# IrDA_Contador_v1_0.net
KiCad netlist of a schematic drawn in EAGLE
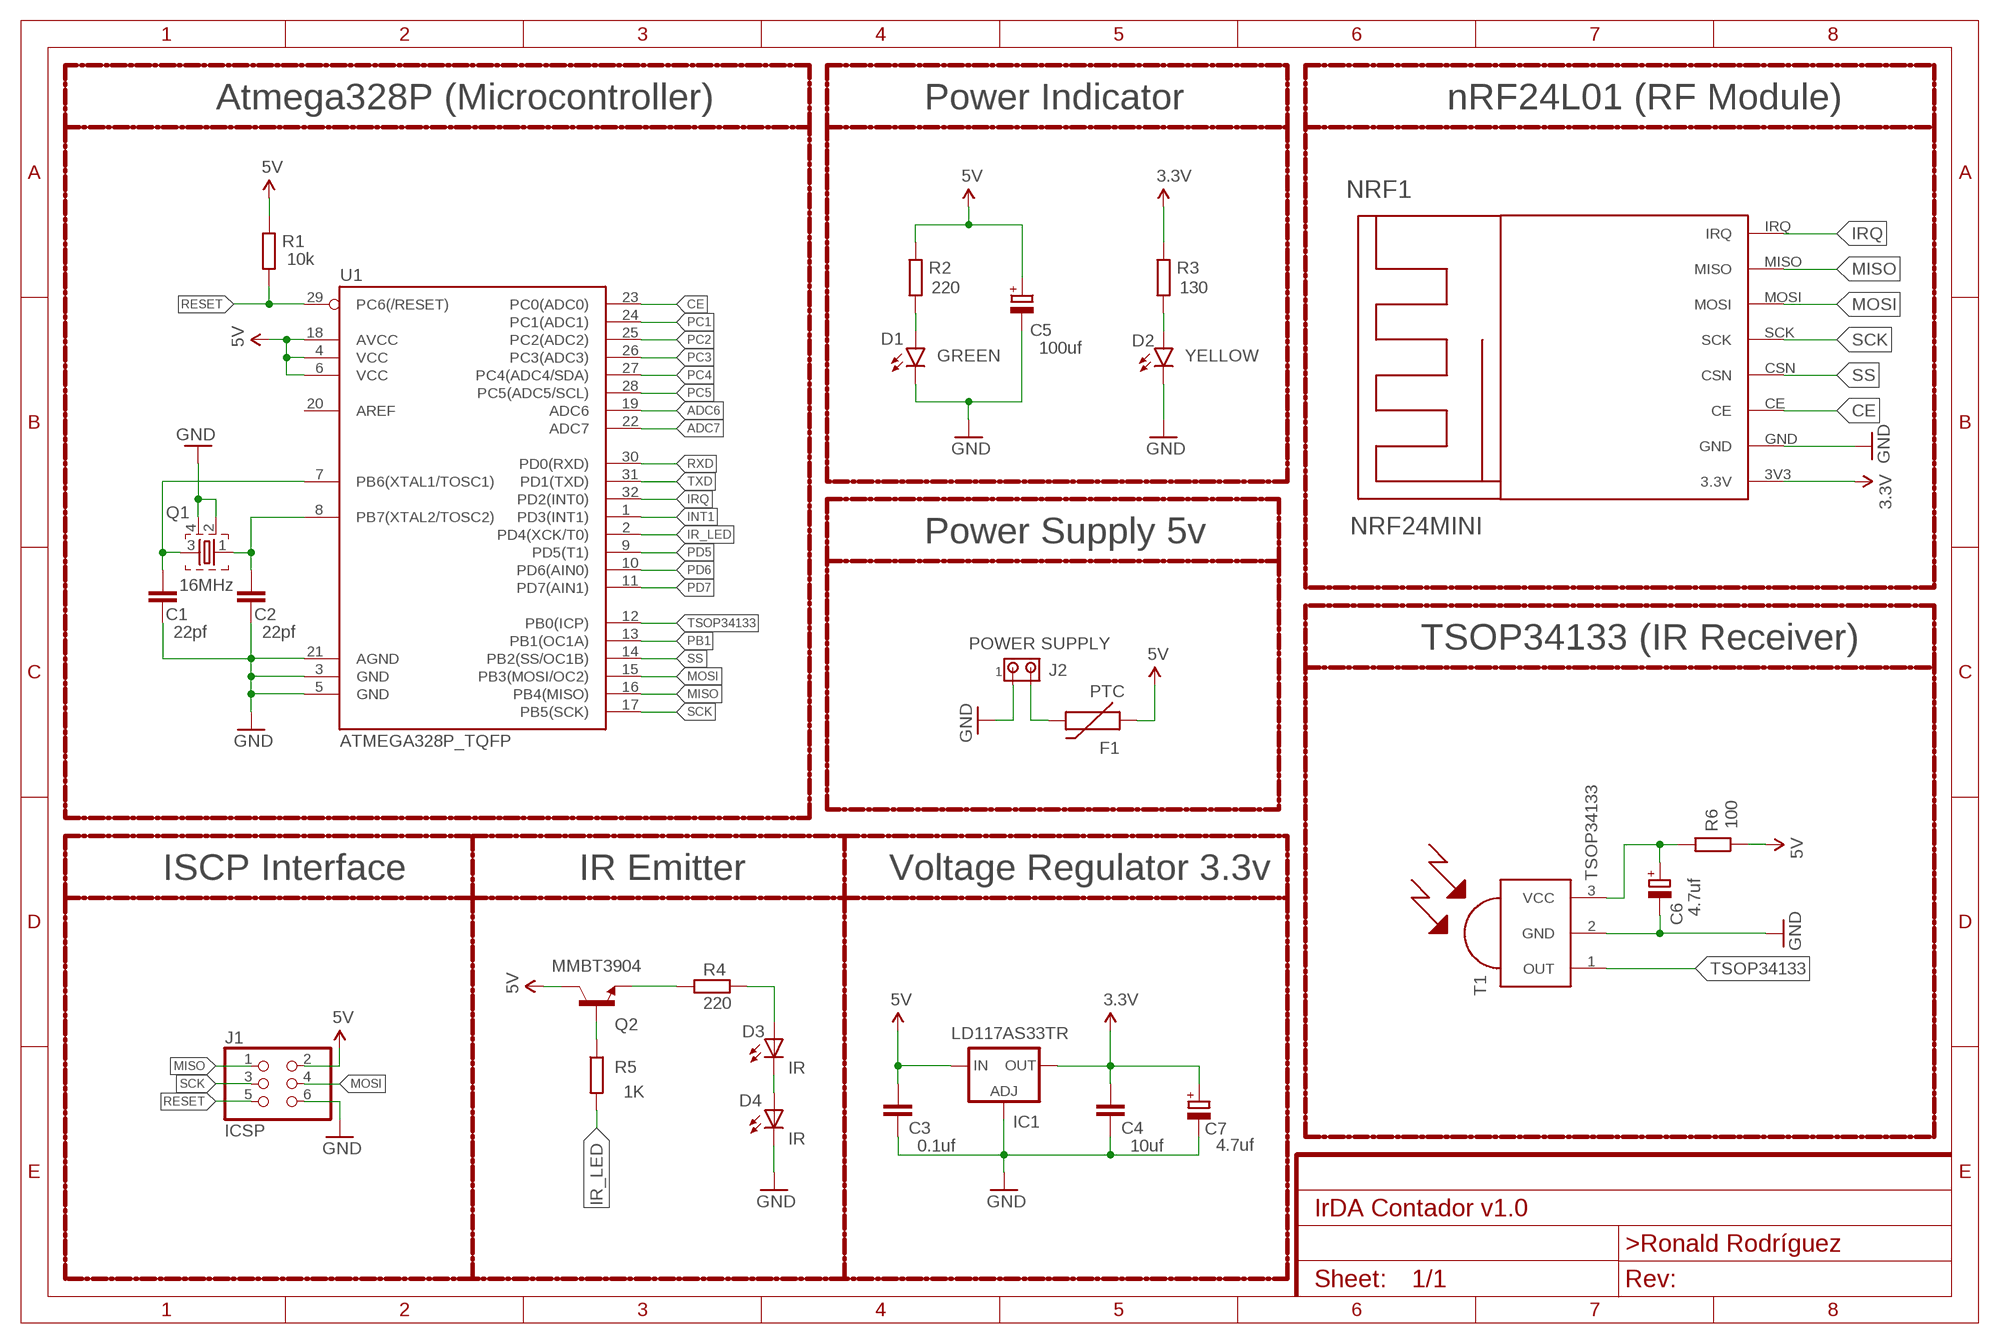
[diagram p0: schematic, sheet 1]

(export (version "E")
  (design (tool "Eeschema 10.0.6"))
  (components
    (comp (ref "C1")
      (value "22pf")
      (footprint "eagle-import:C0603")
      (libsource (lib "eagle-import") (part "C-EUC0603"))
    )
    (comp (ref "C2")
      (value "22pf")
      (footprint "eagle-import:C0603")
      (libsource (lib "eagle-import") (part "C-EUC0603"))
    )
    (comp (ref "C3")
      (value "0.1uf")
      (footprint "eagle-import:C0603")
      (libsource (lib "eagle-import") (part "C-EUC0603"))
    )
    (comp (ref "C4")
      (value "10uf")
      (footprint "eagle-import:C0603")
      (libsource (lib "eagle-import") (part "C-EUC0603"))
    )
    (comp (ref "C5")
      (value "100uf")
      (footprint "eagle-import:153CLV-0605")
      (libsource (lib "eagle-import") (part "CPOL-EU153CLV-0605"))
    )
    (comp (ref "C6")
      (value "4.7uf")
      (footprint "eagle-import:SMC_A")
      (libsource (lib "eagle-import") (part "resistor_CPOL-EUSMCA"))
    )
    (comp (ref "C7")
      (value "4.7uf")
      (footprint "eagle-import:SMC_A")
      (libsource (lib "eagle-import") (part "resistor_CPOL-EUSMCA"))
    )
    (comp (ref "D1")
      (value "GREEN")
      (footprint "eagle-import:LED-0603")
      (libsource (lib "eagle-import") (part "LED-BLUE0603"))
    )
    (comp (ref "D2")
      (value "YELLOW")
      (footprint "eagle-import:LED-0603")
      (libsource (lib "eagle-import") (part "LED-GREEN0603"))
    )
    (comp (ref "D3")
      (value "IR")
      (footprint "eagle-import:LED5MM")
      (libsource (lib "eagle-import") (part "LED5MM"))
    )
    (comp (ref "D4")
      (value "IR")
      (footprint "eagle-import:LED5MM")
      (libsource (lib "eagle-import") (part "LED5MM"))
    )
    (comp (ref "F1")
      (value "PTC")
      (footprint "eagle-import:0603")
      (libsource (lib "eagle-import") (part "PTC0603"))
    )
    (comp (ref "IC1")
      (value "LD117AS33TR")
      (footprint "eagle-import:SOT223")
      (libsource (lib "eagle-import") (part "LD117A?S33TR"))
    )
    (comp (ref "J1")
      (value "ICSP")
      (footprint "eagle-import:2X03")
      (libsource (lib "eagle-import") (part "PINHD-2X3"))
    )
    (comp (ref "J2")
      (value "POWER SUPPLY")
      (footprint "eagle-import:1X2MTA")
      (libsource (lib "eagle-import") (part "MTA02-156"))
    )
    (comp (ref "NRF1")
      (value "NRF24MINI")
      (footprint "eagle-import:NRF24MINI")
      (libsource (lib "eagle-import") (part "NRF24MINI"))
    )
    (comp (ref "Q1")
      (value "16MHz")
      (footprint "eagle-import:FA-20H")
      (libsource (lib "eagle-import") (part "FA-20H"))
    )
    (comp (ref "Q2")
      (value "MMBT3904")
      (footprint "eagle-import:SOT23-3")
      (libsource (lib "eagle-import") (part "TRANSISTOR_NPNMMBT2222A"))
    )
    (comp (ref "R1")
      (value "10k")
      (footprint "eagle-import:R0603")
      (libsource (lib "eagle-import") (part "R-EU_R0603"))
    )
    (comp (ref "R2")
      (value "220")
      (footprint "eagle-import:R0603")
      (libsource (lib "eagle-import") (part "R-EU_R0603"))
    )
    (comp (ref "R3")
      (value "130")
      (footprint "eagle-import:R0603")
      (libsource (lib "eagle-import") (part "R-EU_R0603"))
    )
    (comp (ref "R4")
      (value "220")
      (footprint "eagle-import:R0603")
      (libsource (lib "eagle-import") (part "R-EU_R0603"))
    )
    (comp (ref "R5")
      (value "1K")
      (footprint "eagle-import:R0603")
      (libsource (lib "eagle-import") (part "R-EU_R0603"))
    )
    (comp (ref "R6")
      (value "100")
      (footprint "eagle-import:R0603")
      (libsource (lib "eagle-import") (part "R-EU_R0603"))
    )
    (comp (ref "T1")
      (value "TSOP34133")
      (footprint "eagle-import:TSOP34133")
      (libsource (lib "eagle-import") (part "TSOP34133"))
    )
    (comp (ref "U1")
      (value "ATMEGA328P_TQFP")
      (footprint "eagle-import:TQFP32-08")
      (libsource (lib "eagle-import") (part "ATMEGA328P_TQFP"))
    )
  )
  (nets
    (net (code "1") (name "3.3V") (class "Default")
      (node (ref "C4") (pin "2") (pinfunction "2_2") (pintype "passive"))
      (node (ref "C7") (pin "+") (pinfunction "+_+") (pintype "passive"))
      (node (ref "IC1") (pin "4") (pinfunction "OUT_4") (pintype "passive"))
      (node (ref "NRF1") (pin "3V3") (pinfunction "3.3V_3V3") (pintype "bidirectional"))
      (node (ref "R3") (pin "2") (pinfunction "2_2") (pintype "passive"))
    )
    (net (code "2") (name "5V") (class "Default")
      (node (ref "C3") (pin "2") (pinfunction "2_2") (pintype "passive"))
      (node (ref "C5") (pin "+") (pinfunction "+_+") (pintype "passive"))
      (node (ref "F1") (pin "1") (pinfunction "1_1") (pintype "bidirectional"))
      (node (ref "IC1") (pin "3") (pinfunction "IN_3") (pintype "input"))
      (node (ref "J1") (pin "2") (pinfunction "2_2") (pintype "passive"))
      (node (ref "Q2") (pin "3") (pinfunction "C_3") (pintype "passive"))
      (node (ref "R1") (pin "2") (pinfunction "2_2") (pintype "passive"))
      (node (ref "R2") (pin "2") (pinfunction "2_2") (pintype "passive"))
      (node (ref "R6") (pin "1") (pinfunction "1_1") (pintype "passive"))
      (node (ref "U1") (pin "18") (pinfunction "AVCC_18") (pintype "bidirectional"))
      (node (ref "U1") (pin "4") (pinfunction "VCC_4") (pintype "bidirectional"))
      (node (ref "U1") (pin "6") (pinfunction "VCC_6") (pintype "bidirectional"))
    )
    (net (code "3") (name "ADC6") (class "Default")
      (node (ref "U1") (pin "19") (pinfunction "ADC6_19") (pintype "bidirectional"))
    )
    (net (code "4") (name "ADC7") (class "Default")
      (node (ref "U1") (pin "22") (pinfunction "ADC7_22") (pintype "bidirectional"))
    )
    (net (code "5") (name "CE") (class "Default")
      (node (ref "NRF1") (pin "CE") (pinfunction "CE_CE") (pintype "bidirectional"))
      (node (ref "U1") (pin "23") (pinfunction "PC0(ADC0)_23") (pintype "bidirectional"))
    )
    (net (code "6") (name "GND") (class "Default")
      (node (ref "C1") (pin "1") (pinfunction "1_1") (pintype "passive"))
      (node (ref "C2") (pin "1") (pinfunction "1_1") (pintype "passive"))
      (node (ref "C3") (pin "1") (pinfunction "1_1") (pintype "passive"))
      (node (ref "C4") (pin "1") (pinfunction "1_1") (pintype "passive"))
      (node (ref "C5") (pin "-") (pinfunction "-_-") (pintype "passive"))
      (node (ref "C6") (pin "-") (pinfunction "-_-") (pintype "passive"))
      (node (ref "C7") (pin "-") (pinfunction "-_-") (pintype "passive"))
      (node (ref "D1") (pin "C") (pinfunction "C_C") (pintype "passive"))
      (node (ref "D2") (pin "C") (pinfunction "C_C") (pintype "passive"))
      (node (ref "D4") (pin "K") (pinfunction "C_K") (pintype "passive"))
      (node (ref "IC1") (pin "1") (pinfunction "ADJ_1") (pintype "input"))
      (node (ref "J1") (pin "6") (pinfunction "6_6") (pintype "passive"))
      (node (ref "J2") (pin "1") (pinfunction "1_1") (pintype "passive"))
      (node (ref "NRF1") (pin "GND") (pinfunction "GND_GND") (pintype "bidirectional"))
      (node (ref "Q1") (pin "2") (pinfunction "2_2") (pintype "passive"))
      (node (ref "Q1") (pin "4") (pinfunction "4_4") (pintype "passive"))
      (node (ref "T1") (pin "2") (pinfunction "GND_2") (pintype "bidirectional"))
      (node (ref "U1") (pin "21") (pinfunction "AGND_21") (pintype "bidirectional"))
      (node (ref "U1") (pin "3") (pinfunction "GND_3") (pintype "bidirectional"))
      (node (ref "U1") (pin "5") (pinfunction "GND_5") (pintype "bidirectional"))
    )
    (net (code "7") (name "INT1") (class "Default")
      (node (ref "U1") (pin "1") (pinfunction "PD3(INT1)_1") (pintype "bidirectional"))
    )
    (net (code "8") (name "IRQ") (class "Default")
      (node (ref "NRF1") (pin "IRQ") (pinfunction "IRQ_IRQ") (pintype "bidirectional"))
      (node (ref "U1") (pin "32") (pinfunction "PD2(INT0)_32") (pintype "bidirectional"))
    )
    (net (code "9") (name "IR_LED") (class "Default")
      (node (ref "R5") (pin "2") (pinfunction "2_2") (pintype "passive"))
      (node (ref "U1") (pin "2") (pinfunction "PD4(XCK/T0)_2") (pintype "bidirectional"))
    )
    (net (code "10") (name "MISO") (class "Default")
      (node (ref "J1") (pin "1") (pinfunction "1_1") (pintype "passive"))
      (node (ref "NRF1") (pin "MISO") (pinfunction "MISO_MISO") (pintype "bidirectional"))
      (node (ref "U1") (pin "16") (pinfunction "PB4(MISO)_16") (pintype "bidirectional"))
    )
    (net (code "11") (name "MOSI") (class "Default")
      (node (ref "J1") (pin "4") (pinfunction "4_4") (pintype "passive"))
      (node (ref "NRF1") (pin "MOSI") (pinfunction "MOSI_MOSI") (pintype "bidirectional"))
      (node (ref "U1") (pin "15") (pinfunction "PB3(MOSI/OC2)_15") (pintype "bidirectional"))
    )
    (net (code "12") (name "Net-(D1-PadA)") (class "Default")
      (node (ref "D1") (pin "A") (pinfunction "A_A") (pintype "passive"))
      (node (ref "R2") (pin "1") (pinfunction "1_1") (pintype "passive"))
    )
    (net (code "13") (name "Net-(D2-PadA)") (class "Default")
      (node (ref "D2") (pin "A") (pinfunction "A_A") (pintype "passive"))
      (node (ref "R3") (pin "1") (pinfunction "1_1") (pintype "passive"))
    )
    (net (code "14") (name "Net-(D3-C)") (class "Default")
      (node (ref "D3") (pin "K") (pinfunction "C_K") (pintype "passive"))
      (node (ref "D4") (pin "A") (pinfunction "A_A") (pintype "passive"))
    )
    (net (code "15") (name "Net-(D3-PadA)") (class "Default")
      (node (ref "D3") (pin "A") (pinfunction "A_A") (pintype "passive"))
      (node (ref "R4") (pin "1") (pinfunction "1_1") (pintype "passive"))
    )
    (net (code "16") (name "Net-(F1-Pad2)") (class "Default")
      (node (ref "F1") (pin "2") (pinfunction "2_2") (pintype "bidirectional"))
      (node (ref "J2") (pin "2") (pinfunction "2_2") (pintype "passive"))
    )
    (net (code "17") (name "Net-(Q2-B)") (class "Default")
      (node (ref "Q2") (pin "1") (pinfunction "B_1") (pintype "passive"))
      (node (ref "R5") (pin "1") (pinfunction "1_1") (pintype "passive"))
    )
    (net (code "18") (name "Net-(Q2-E)") (class "Default")
      (node (ref "Q2") (pin "2") (pinfunction "E_2") (pintype "passive"))
      (node (ref "R4") (pin "2") (pinfunction "2_2") (pintype "passive"))
    )
    (net (code "19") (name "Net-(T1-VCC)") (class "Default")
      (node (ref "C6") (pin "+") (pinfunction "+_+") (pintype "passive"))
      (node (ref "R6") (pin "2") (pinfunction "2_2") (pintype "passive"))
      (node (ref "T1") (pin "3") (pinfunction "VCC_3") (pintype "bidirectional"))
    )
    (net (code "20") (name "Net-(U1-PB6(XTAL1{slash}TOSC1))") (class "Default")
      (node (ref "C1") (pin "2") (pinfunction "2_2") (pintype "passive"))
      (node (ref "Q1") (pin "3") (pinfunction "3_3") (pintype "passive"))
      (node (ref "U1") (pin "7") (pinfunction "PB6(XTAL1/TOSC1)_7") (pintype "bidirectional"))
    )
    (net (code "21") (name "Net-(U1-PB7(XTAL2{slash}TOSC2))") (class "Default")
      (node (ref "C2") (pin "2") (pinfunction "2_2") (pintype "passive"))
      (node (ref "Q1") (pin "1") (pinfunction "1_1") (pintype "passive"))
      (node (ref "U1") (pin "8") (pinfunction "PB7(XTAL2/TOSC2)_8") (pintype "bidirectional"))
    )
    (net (code "22") (name "PB1") (class "Default")
      (node (ref "U1") (pin "13") (pinfunction "PB1(OC1A)_13") (pintype "bidirectional"))
    )
    (net (code "23") (name "PC1") (class "Default")
      (node (ref "U1") (pin "24") (pinfunction "PC1(ADC1)_24") (pintype "bidirectional"))
    )
    (net (code "24") (name "PC2") (class "Default")
      (node (ref "U1") (pin "25") (pinfunction "PC2(ADC2)_25") (pintype "bidirectional"))
    )
    (net (code "25") (name "PC3") (class "Default")
      (node (ref "U1") (pin "26") (pinfunction "PC3(ADC3)_26") (pintype "bidirectional"))
    )
    (net (code "26") (name "PC4") (class "Default")
      (node (ref "U1") (pin "27") (pinfunction "PC4(ADC4/SDA)_27") (pintype "bidirectional"))
    )
    (net (code "27") (name "PC5") (class "Default")
      (node (ref "U1") (pin "28") (pinfunction "PC5(ADC5/SCL)_28") (pintype "bidirectional"))
    )
    (net (code "28") (name "PD5") (class "Default")
      (node (ref "U1") (pin "9") (pinfunction "PD5(T1)_9") (pintype "bidirectional"))
    )
    (net (code "29") (name "PD6") (class "Default")
      (node (ref "U1") (pin "10") (pinfunction "PD6(AIN0)_10") (pintype "bidirectional"))
    )
    (net (code "30") (name "PD7") (class "Default")
      (node (ref "U1") (pin "11") (pinfunction "PD7(AIN1)_11") (pintype "bidirectional"))
    )
    (net (code "31") (name "RESET") (class "Default")
      (node (ref "J1") (pin "5") (pinfunction "5_5") (pintype "passive"))
      (node (ref "R1") (pin "1") (pinfunction "1_1") (pintype "passive"))
      (node (ref "U1") (pin "29") (pinfunction "PC6(/RESET)_29") (pintype "bidirectional"))
    )
    (net (code "32") (name "RXD") (class "Default")
      (node (ref "U1") (pin "30") (pinfunction "PD0(RXD)_30") (pintype "bidirectional"))
    )
    (net (code "33") (name "SCK") (class "Default")
      (node (ref "J1") (pin "3") (pinfunction "3_3") (pintype "passive"))
      (node (ref "NRF1") (pin "SCK") (pinfunction "SCK_SCK") (pintype "bidirectional"))
      (node (ref "U1") (pin "17") (pinfunction "PB5(SCK)_17") (pintype "bidirectional"))
    )
    (net (code "34") (name "SS") (class "Default")
      (node (ref "NRF1") (pin "CSN") (pinfunction "CSN_CSN") (pintype "bidirectional"))
      (node (ref "U1") (pin "14") (pinfunction "PB2(SS/OC1B)_14") (pintype "bidirectional"))
    )
    (net (code "35") (name "TSOP34133") (class "Default")
      (node (ref "T1") (pin "1") (pinfunction "OUT_1") (pintype "bidirectional"))
      (node (ref "U1") (pin "12") (pinfunction "PB0(ICP)_12") (pintype "bidirectional"))
    )
    (net (code "36") (name "TXD") (class "Default")
      (node (ref "U1") (pin "31") (pinfunction "PD1(TXD)_31") (pintype "bidirectional"))
    )
    (net (code "37") (name "unconnected-(U1-AREF-Pad20)") (class "Default")
      (node (ref "U1") (pin "20") (pinfunction "AREF_20") (pintype "bidirectional"))
    )
  )
)
